# 50_Distance.net
KiCad netlist of a schematic drawn in Altium Designer
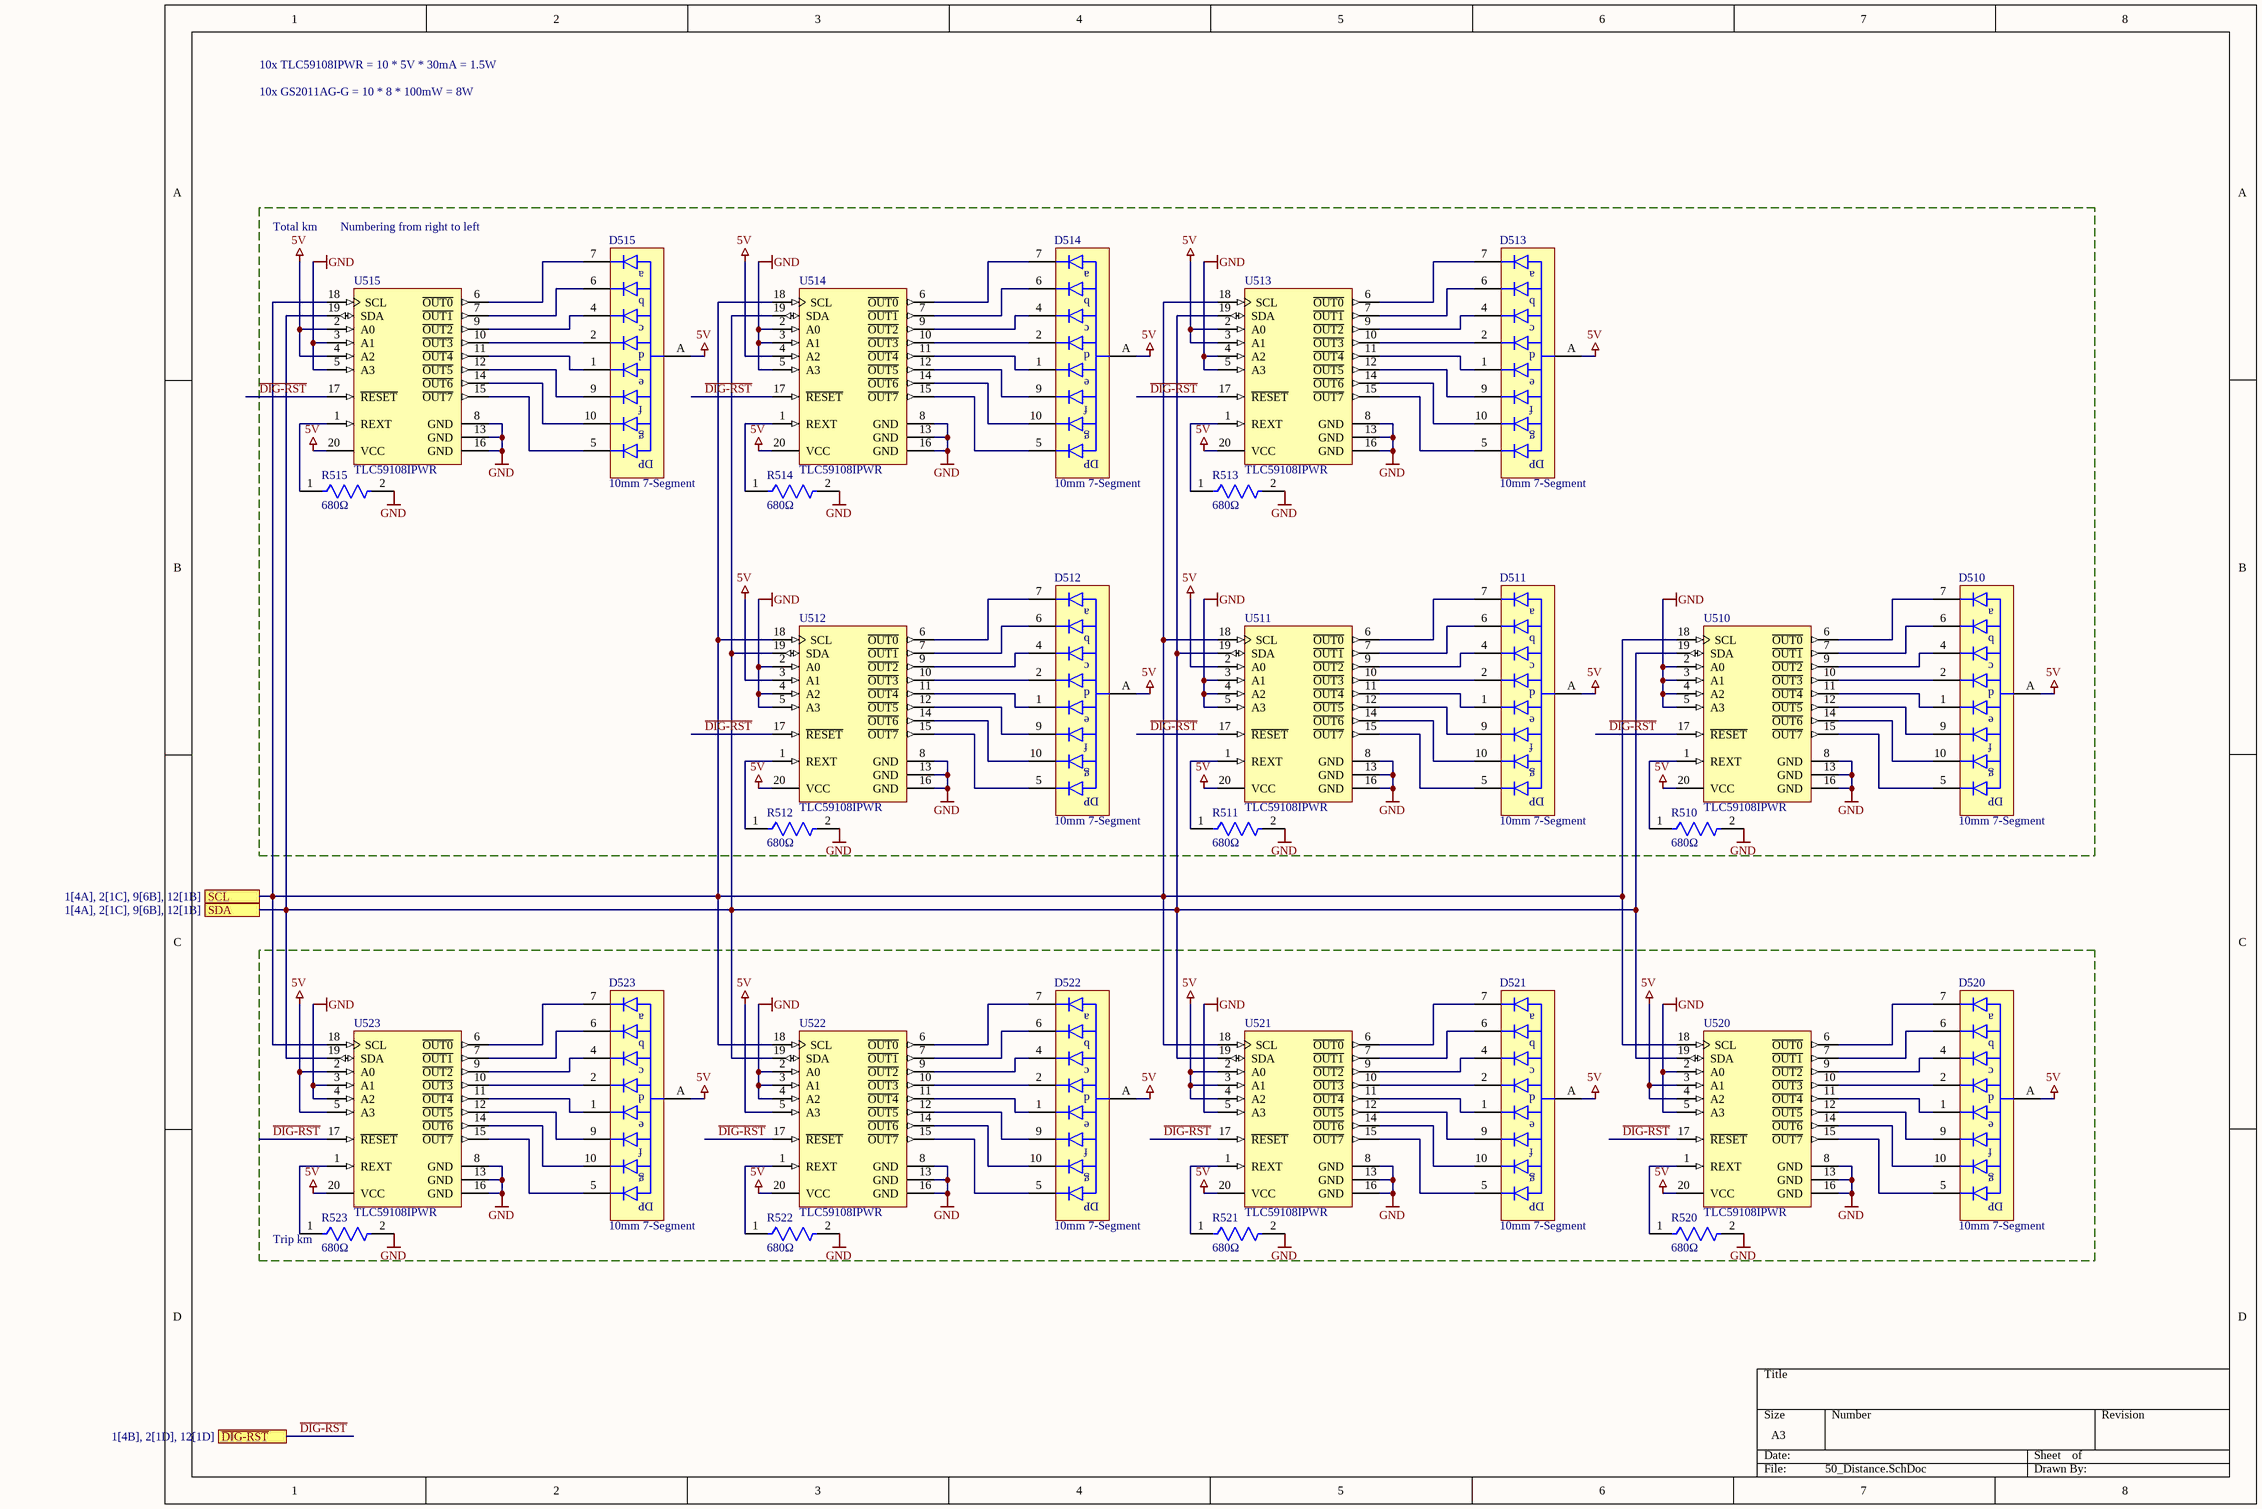
[diagram p0: 50_Distance.SchDoc]

(export (version "E")
  (design (tool "Eeschema 10.0.6"))
  (components
    (comp (ref "D510")
      (value "10mm 7-Segment")
      (footprint "GS2011AG-G")
      (description "SMD, 10x6.9mm 7-Segment")
      (libsource (lib "AltiumLib_MILUTIN") (part "GS2011AG-G"))
    )
    (comp (ref "D511")
      (value "10mm 7-Segment")
      (footprint "GS2011AG-G")
      (description "SMD, 10x6.9mm 7-Segment")
      (libsource (lib "AltiumLib_MILUTIN") (part "GS2011AG-G"))
    )
    (comp (ref "D512")
      (value "10mm 7-Segment")
      (footprint "GS2011AG-G")
      (description "SMD, 10x6.9mm 7-Segment")
      (libsource (lib "AltiumLib_MILUTIN") (part "GS2011AG-G"))
    )
    (comp (ref "D513")
      (value "10mm 7-Segment")
      (footprint "GS2011AG-G")
      (description "SMD, 10x6.9mm 7-Segment")
      (libsource (lib "AltiumLib_MILUTIN") (part "GS2011AG-G"))
    )
    (comp (ref "D514")
      (value "10mm 7-Segment")
      (footprint "GS2011AG-G")
      (description "SMD, 10x6.9mm 7-Segment")
      (libsource (lib "AltiumLib_MILUTIN") (part "GS2011AG-G"))
    )
    (comp (ref "D515")
      (value "10mm 7-Segment")
      (footprint "GS2011AG-G")
      (description "SMD, 10x6.9mm 7-Segment")
      (libsource (lib "AltiumLib_MILUTIN") (part "GS2011AG-G"))
    )
    (comp (ref "D520")
      (value "10mm 7-Segment")
      (footprint "GS2011AG-G")
      (description "SMD, 10x6.9mm 7-Segment")
      (libsource (lib "AltiumLib_MILUTIN") (part "GS2011AG-G"))
    )
    (comp (ref "D521")
      (value "10mm 7-Segment")
      (footprint "GS2011AG-G")
      (description "SMD, 10x6.9mm 7-Segment")
      (libsource (lib "AltiumLib_MILUTIN") (part "GS2011AG-G"))
    )
    (comp (ref "D522")
      (value "10mm 7-Segment")
      (footprint "GS2011AG-G")
      (description "SMD, 10x6.9mm 7-Segment")
      (libsource (lib "AltiumLib_MILUTIN") (part "GS2011AG-G"))
    )
    (comp (ref "D523")
      (value "10mm 7-Segment")
      (footprint "GS2011AG-G")
      (description "SMD, 10x6.9mm 7-Segment")
      (libsource (lib "AltiumLib_MILUTIN") (part "GS2011AG-G"))
    )
    (comp (ref "R510")
      (value "680Ω")
      (footprint "FP-CRCW0603-e3-IPC_A")
      (description "RES Thick Film, 680Ω, 5%, 0.1W, 200ppm/°C, 0603\r\nCRCW0603680RJNEA")
      (fields (field (name "TOLERANCE") "5%"))
      (libsource (lib "Altium Content Vault") (part "1029c3af85768c4190bb7ad29bc67b5"))
    )
    (comp (ref "R511")
      (value "680Ω")
      (footprint "FP-CRCW0603-e3-IPC_A")
      (description "RES Thick Film, 680Ω, 5%, 0.1W, 200ppm/°C, 0603\r\nCRCW0603680RJNEA")
      (fields (field (name "TOLERANCE") "5%"))
      (libsource (lib "Altium Content Vault") (part "1029c3af85768c4190bb7ad29bc67b5"))
    )
    (comp (ref "R512")
      (value "680Ω")
      (footprint "FP-CRCW0603-e3-IPC_A")
      (description "RES Thick Film, 680Ω, 5%, 0.1W, 200ppm/°C, 0603\r\nCRCW0603680RJNEA")
      (fields (field (name "TOLERANCE") "5%"))
      (libsource (lib "Altium Content Vault") (part "1029c3af85768c4190bb7ad29bc67b5"))
    )
    (comp (ref "R513")
      (value "680Ω")
      (footprint "FP-CRCW0603-e3-IPC_A")
      (description "RES Thick Film, 680Ω, 5%, 0.1W, 200ppm/°C, 0603\r\nCRCW0603680RJNEA")
      (fields (field (name "TOLERANCE") "5%"))
      (libsource (lib "Altium Content Vault") (part "1029c3af85768c4190bb7ad29bc67b5"))
    )
    (comp (ref "R514")
      (value "680Ω")
      (footprint "FP-CRCW0603-e3-IPC_A")
      (description "RES Thick Film, 680Ω, 5%, 0.1W, 200ppm/°C, 0603\r\nCRCW0603680RJNEA")
      (fields (field (name "TOLERANCE") "5%"))
      (libsource (lib "Altium Content Vault") (part "1029c3af85768c4190bb7ad29bc67b5"))
    )
    (comp (ref "R515")
      (value "680Ω")
      (footprint "FP-CRCW0603-e3-IPC_A")
      (description "RES Thick Film, 680Ω, 5%, 0.1W, 200ppm/°C, 0603\r\nCRCW0603680RJNEA")
      (fields (field (name "TOLERANCE") "5%"))
      (libsource (lib "Altium Content Vault") (part "1029c3af85768c4190bb7ad29bc67b5"))
    )
    (comp (ref "R520")
      (value "680Ω")
      (footprint "FP-CRCW0603-e3-IPC_A")
      (description "RES Thick Film, 680Ω, 5%, 0.1W, 200ppm/°C, 0603\r\nCRCW0603680RJNEA")
      (fields (field (name "TOLERANCE") "5%"))
      (libsource (lib "Altium Content Vault") (part "1029c3af85768c4190bb7ad29bc67b5"))
    )
    (comp (ref "R521")
      (value "680Ω")
      (footprint "FP-CRCW0603-e3-IPC_A")
      (description "RES Thick Film, 680Ω, 5%, 0.1W, 200ppm/°C, 0603\r\nCRCW0603680RJNEA")
      (fields (field (name "TOLERANCE") "5%"))
      (libsource (lib "Altium Content Vault") (part "1029c3af85768c4190bb7ad29bc67b5"))
    )
    (comp (ref "R522")
      (value "680Ω")
      (footprint "FP-CRCW0603-e3-IPC_A")
      (description "RES Thick Film, 680Ω, 5%, 0.1W, 200ppm/°C, 0603\r\nCRCW0603680RJNEA")
      (fields (field (name "TOLERANCE") "5%"))
      (libsource (lib "Altium Content Vault") (part "1029c3af85768c4190bb7ad29bc67b5"))
    )
    (comp (ref "R523")
      (value "680Ω")
      (footprint "FP-CRCW0603-e3-IPC_A")
      (description "RES Thick Film, 680Ω, 5%, 0.1W, 200ppm/°C, 0603\r\nCRCW0603680RJNEA")
      (fields (field (name "TOLERANCE") "5%"))
      (libsource (lib "Altium Content Vault") (part "1029c3af85768c4190bb7ad29bc67b5"))
    )
    (comp (ref "U510")
      (value "TLC59108IPWR")
      (footprint "PW0020A_M")
      (fields (field (name "MANUFACTURER") "Texas Instruments"))
      (libsource (lib "Altium Content Vault") (part "TI-TLC59108PW20"))
    )
    (comp (ref "U511")
      (value "TLC59108IPWR")
      (footprint "PW0020A_M")
      (fields (field (name "MANUFACTURER") "Texas Instruments"))
      (libsource (lib "Altium Content Vault") (part "TI-TLC59108PW20"))
    )
    (comp (ref "U512")
      (value "TLC59108IPWR")
      (footprint "PW0020A_M")
      (fields (field (name "MANUFACTURER") "Texas Instruments"))
      (libsource (lib "Altium Content Vault") (part "TI-TLC59108PW20"))
    )
    (comp (ref "U513")
      (value "TLC59108IPWR")
      (footprint "PW0020A_M")
      (fields (field (name "MANUFACTURER") "Texas Instruments"))
      (libsource (lib "Altium Content Vault") (part "TI-TLC59108PW20"))
    )
    (comp (ref "U514")
      (value "TLC59108IPWR")
      (footprint "PW0020A_M")
      (fields (field (name "MANUFACTURER") "Texas Instruments"))
      (libsource (lib "Altium Content Vault") (part "TI-TLC59108PW20"))
    )
    (comp (ref "U515")
      (value "TLC59108IPWR")
      (footprint "PW0020A_M")
      (fields (field (name "MANUFACTURER") "Texas Instruments"))
      (libsource (lib "Altium Content Vault") (part "TI-TLC59108PW20"))
    )
    (comp (ref "U520")
      (value "TLC59108IPWR")
      (footprint "PW0020A_M")
      (fields (field (name "MANUFACTURER") "Texas Instruments"))
      (libsource (lib "Altium Content Vault") (part "TI-TLC59108PW20"))
    )
    (comp (ref "U521")
      (value "TLC59108IPWR")
      (footprint "PW0020A_M")
      (fields (field (name "MANUFACTURER") "Texas Instruments"))
      (libsource (lib "Altium Content Vault") (part "TI-TLC59108PW20"))
    )
    (comp (ref "U522")
      (value "TLC59108IPWR")
      (footprint "PW0020A_M")
      (fields (field (name "MANUFACTURER") "Texas Instruments"))
      (libsource (lib "Altium Content Vault") (part "TI-TLC59108PW20"))
    )
    (comp (ref "U523")
      (value "TLC59108IPWR")
      (footprint "PW0020A_M")
      (fields (field (name "MANUFACTURER") "Texas Instruments"))
      (libsource (lib "Altium Content Vault") (part "TI-TLC59108PW20"))
    )
  )
  (nets
    (net (code "1") (name "/SCL") (class "Default")
      (node (ref "U510") (pin "18") (pinfunction "SCL_18") (pintype "input"))
      (node (ref "U511") (pin "18") (pinfunction "SCL_18") (pintype "input"))
      (node (ref "U512") (pin "18") (pinfunction "SCL_18") (pintype "input"))
      (node (ref "U513") (pin "18") (pinfunction "SCL_18") (pintype "input"))
      (node (ref "U514") (pin "18") (pinfunction "SCL_18") (pintype "input"))
      (node (ref "U515") (pin "18") (pinfunction "SCL_18") (pintype "input"))
      (node (ref "U520") (pin "18") (pinfunction "SCL_18") (pintype "input"))
      (node (ref "U521") (pin "18") (pinfunction "SCL_18") (pintype "input"))
      (node (ref "U522") (pin "18") (pinfunction "SCL_18") (pintype "input"))
      (node (ref "U523") (pin "18") (pinfunction "SCL_18") (pintype "input"))
    )
    (net (code "2") (name "/SDA") (class "Default")
      (node (ref "U510") (pin "19") (pinfunction "SDA_19") (pintype "bidirectional"))
      (node (ref "U511") (pin "19") (pinfunction "SDA_19") (pintype "bidirectional"))
      (node (ref "U512") (pin "19") (pinfunction "SDA_19") (pintype "bidirectional"))
      (node (ref "U513") (pin "19") (pinfunction "SDA_19") (pintype "bidirectional"))
      (node (ref "U514") (pin "19") (pinfunction "SDA_19") (pintype "bidirectional"))
      (node (ref "U515") (pin "19") (pinfunction "SDA_19") (pintype "bidirectional"))
      (node (ref "U520") (pin "19") (pinfunction "SDA_19") (pintype "bidirectional"))
      (node (ref "U521") (pin "19") (pinfunction "SDA_19") (pintype "bidirectional"))
      (node (ref "U522") (pin "19") (pinfunction "SDA_19") (pintype "bidirectional"))
      (node (ref "U523") (pin "19") (pinfunction "SDA_19") (pintype "bidirectional"))
    )
    (net (code "3") (name "/~{DIG-RST}") (class "Default")
      (node (ref "U510") (pin "17") (pinfunction "~{RESET}_17") (pintype "input"))
      (node (ref "U511") (pin "17") (pinfunction "~{RESET}_17") (pintype "input"))
      (node (ref "U512") (pin "17") (pinfunction "~{RESET}_17") (pintype "input"))
      (node (ref "U513") (pin "17") (pinfunction "~{RESET}_17") (pintype "input"))
      (node (ref "U514") (pin "17") (pinfunction "~{RESET}_17") (pintype "input"))
      (node (ref "U515") (pin "17") (pinfunction "~{RESET}_17") (pintype "input"))
      (node (ref "U520") (pin "17") (pinfunction "~{RESET}_17") (pintype "input"))
      (node (ref "U521") (pin "17") (pinfunction "~{RESET}_17") (pintype "input"))
      (node (ref "U522") (pin "17") (pinfunction "~{RESET}_17") (pintype "input"))
      (node (ref "U523") (pin "17") (pinfunction "~{RESET}_17") (pintype "input"))
    )
    (net (code "4") (name "5V") (class "Default")
      (node (ref "D510") (pin "A") (pinfunction "A_A") (pintype "passive"))
      (node (ref "D511") (pin "A") (pinfunction "A_A") (pintype "passive"))
      (node (ref "D512") (pin "A") (pinfunction "A_A") (pintype "passive"))
      (node (ref "D513") (pin "A") (pinfunction "A_A") (pintype "passive"))
      (node (ref "D514") (pin "A") (pinfunction "A_A") (pintype "passive"))
      (node (ref "D515") (pin "A") (pinfunction "A_A") (pintype "passive"))
      (node (ref "D520") (pin "A") (pinfunction "A_A") (pintype "passive"))
      (node (ref "D521") (pin "A") (pinfunction "A_A") (pintype "passive"))
      (node (ref "D522") (pin "A") (pinfunction "A_A") (pintype "passive"))
      (node (ref "D523") (pin "A") (pinfunction "A_A") (pintype "passive"))
      (node (ref "U510") (pin "20") (pinfunction "VCC_20") (pintype "power_in"))
      (node (ref "U511") (pin "2") (pinfunction "A0_2") (pintype "input"))
      (node (ref "U511") (pin "20") (pinfunction "VCC_20") (pintype "power_in"))
      (node (ref "U512") (pin "20") (pinfunction "VCC_20") (pintype "power_in"))
      (node (ref "U512") (pin "3") (pinfunction "A1_3") (pintype "input"))
      (node (ref "U513") (pin "2") (pinfunction "A0_2") (pintype "input"))
      (node (ref "U513") (pin "20") (pinfunction "VCC_20") (pintype "power_in"))
      (node (ref "U513") (pin "3") (pinfunction "A1_3") (pintype "input"))
      (node (ref "U514") (pin "20") (pinfunction "VCC_20") (pintype "power_in"))
      (node (ref "U514") (pin "4") (pinfunction "A2_4") (pintype "input"))
      (node (ref "U515") (pin "2") (pinfunction "A0_2") (pintype "input"))
      (node (ref "U515") (pin "20") (pinfunction "VCC_20") (pintype "power_in"))
      (node (ref "U515") (pin "4") (pinfunction "A2_4") (pintype "input"))
      (node (ref "U520") (pin "20") (pinfunction "VCC_20") (pintype "power_in"))
      (node (ref "U520") (pin "3") (pinfunction "A1_3") (pintype "input"))
      (node (ref "U520") (pin "4") (pinfunction "A2_4") (pintype "input"))
      (node (ref "U521") (pin "2") (pinfunction "A0_2") (pintype "input"))
      (node (ref "U521") (pin "20") (pinfunction "VCC_20") (pintype "power_in"))
      (node (ref "U521") (pin "3") (pinfunction "A1_3") (pintype "input"))
      (node (ref "U521") (pin "4") (pinfunction "A2_4") (pintype "input"))
      (node (ref "U522") (pin "20") (pinfunction "VCC_20") (pintype "power_in"))
      (node (ref "U522") (pin "5") (pinfunction "A3_5") (pintype "input"))
      (node (ref "U523") (pin "2") (pinfunction "A0_2") (pintype "input"))
      (node (ref "U523") (pin "20") (pinfunction "VCC_20") (pintype "power_in"))
      (node (ref "U523") (pin "5") (pinfunction "A3_5") (pintype "input"))
    )
    (net (code "5") (name "GND") (class "Default")
      (node (ref "R510") (pin "2") (pinfunction "2_2") (pintype "passive"))
      (node (ref "R511") (pin "2") (pinfunction "2_2") (pintype "passive"))
      (node (ref "R512") (pin "2") (pinfunction "2_2") (pintype "passive"))
      (node (ref "R513") (pin "2") (pinfunction "2_2") (pintype "passive"))
      (node (ref "R514") (pin "2") (pinfunction "2_2") (pintype "passive"))
      (node (ref "R515") (pin "2") (pinfunction "2_2") (pintype "passive"))
      (node (ref "R520") (pin "2") (pinfunction "2_2") (pintype "passive"))
      (node (ref "R521") (pin "2") (pinfunction "2_2") (pintype "passive"))
      (node (ref "R522") (pin "2") (pinfunction "2_2") (pintype "passive"))
      (node (ref "R523") (pin "2") (pinfunction "2_2") (pintype "passive"))
      (node (ref "U510") (pin "13") (pinfunction "GND_13") (pintype "power_in"))
      (node (ref "U510") (pin "16") (pinfunction "GND_16") (pintype "power_in"))
      (node (ref "U510") (pin "2") (pinfunction "A0_2") (pintype "input"))
      (node (ref "U510") (pin "3") (pinfunction "A1_3") (pintype "input"))
      (node (ref "U510") (pin "4") (pinfunction "A2_4") (pintype "input"))
      (node (ref "U510") (pin "5") (pinfunction "A3_5") (pintype "input"))
      (node (ref "U510") (pin "8") (pinfunction "GND_8") (pintype "power_in"))
      (node (ref "U511") (pin "13") (pinfunction "GND_13") (pintype "power_in"))
      (node (ref "U511") (pin "16") (pinfunction "GND_16") (pintype "power_in"))
      (node (ref "U511") (pin "3") (pinfunction "A1_3") (pintype "input"))
      (node (ref "U511") (pin "4") (pinfunction "A2_4") (pintype "input"))
      (node (ref "U511") (pin "5") (pinfunction "A3_5") (pintype "input"))
      (node (ref "U511") (pin "8") (pinfunction "GND_8") (pintype "power_in"))
      (node (ref "U512") (pin "13") (pinfunction "GND_13") (pintype "power_in"))
      (node (ref "U512") (pin "16") (pinfunction "GND_16") (pintype "power_in"))
      (node (ref "U512") (pin "2") (pinfunction "A0_2") (pintype "input"))
      (node (ref "U512") (pin "4") (pinfunction "A2_4") (pintype "input"))
      (node (ref "U512") (pin "5") (pinfunction "A3_5") (pintype "input"))
      (node (ref "U512") (pin "8") (pinfunction "GND_8") (pintype "power_in"))
      (node (ref "U513") (pin "13") (pinfunction "GND_13") (pintype "power_in"))
      (node (ref "U513") (pin "16") (pinfunction "GND_16") (pintype "power_in"))
      (node (ref "U513") (pin "4") (pinfunction "A2_4") (pintype "input"))
      (node (ref "U513") (pin "5") (pinfunction "A3_5") (pintype "input"))
      (node (ref "U513") (pin "8") (pinfunction "GND_8") (pintype "power_in"))
      (node (ref "U514") (pin "13") (pinfunction "GND_13") (pintype "power_in"))
      (node (ref "U514") (pin "16") (pinfunction "GND_16") (pintype "power_in"))
      (node (ref "U514") (pin "2") (pinfunction "A0_2") (pintype "input"))
      (node (ref "U514") (pin "3") (pinfunction "A1_3") (pintype "input"))
      (node (ref "U514") (pin "5") (pinfunction "A3_5") (pintype "input"))
      (node (ref "U514") (pin "8") (pinfunction "GND_8") (pintype "power_in"))
      (node (ref "U515") (pin "13") (pinfunction "GND_13") (pintype "power_in"))
      (node (ref "U515") (pin "16") (pinfunction "GND_16") (pintype "power_in"))
      (node (ref "U515") (pin "3") (pinfunction "A1_3") (pintype "input"))
      (node (ref "U515") (pin "5") (pinfunction "A3_5") (pintype "input"))
      (node (ref "U515") (pin "8") (pinfunction "GND_8") (pintype "power_in"))
      (node (ref "U520") (pin "13") (pinfunction "GND_13") (pintype "power_in"))
      (node (ref "U520") (pin "16") (pinfunction "GND_16") (pintype "power_in"))
      (node (ref "U520") (pin "2") (pinfunction "A0_2") (pintype "input"))
      (node (ref "U520") (pin "5") (pinfunction "A3_5") (pintype "input"))
      (node (ref "U520") (pin "8") (pinfunction "GND_8") (pintype "power_in"))
      (node (ref "U521") (pin "13") (pinfunction "GND_13") (pintype "power_in"))
      (node (ref "U521") (pin "16") (pinfunction "GND_16") (pintype "power_in"))
      (node (ref "U521") (pin "5") (pinfunction "A3_5") (pintype "input"))
      (node (ref "U521") (pin "8") (pinfunction "GND_8") (pintype "power_in"))
      (node (ref "U522") (pin "13") (pinfunction "GND_13") (pintype "power_in"))
      (node (ref "U522") (pin "16") (pinfunction "GND_16") (pintype "power_in"))
      (node (ref "U522") (pin "2") (pinfunction "A0_2") (pintype "input"))
      (node (ref "U522") (pin "3") (pinfunction "A1_3") (pintype "input"))
      (node (ref "U522") (pin "4") (pinfunction "A2_4") (pintype "input"))
      (node (ref "U522") (pin "8") (pinfunction "GND_8") (pintype "power_in"))
      (node (ref "U523") (pin "13") (pinfunction "GND_13") (pintype "power_in"))
      (node (ref "U523") (pin "16") (pinfunction "GND_16") (pintype "power_in"))
      (node (ref "U523") (pin "3") (pinfunction "A1_3") (pintype "input"))
      (node (ref "U523") (pin "4") (pinfunction "A2_4") (pintype "input"))
      (node (ref "U523") (pin "8") (pinfunction "GND_8") (pintype "power_in"))
    )
    (net (code "6") (name "Net-(U510-REXT)") (class "Default")
      (node (ref "R510") (pin "1") (pinfunction "1_1") (pintype "passive"))
      (node (ref "U510") (pin "1") (pinfunction "REXT_1") (pintype "input"))
    )
    (net (code "7") (name "Net-(U510-~{OUT0})") (class "Default")
      (node (ref "D510") (pin "7") (pinfunction "7_7") (pintype "passive"))
      (node (ref "U510") (pin "6") (pinfunction "~{OUT0}_6") (pintype "output"))
    )
    (net (code "8") (name "Net-(U510-~{OUT1})") (class "Default")
      (node (ref "D510") (pin "6") (pinfunction "6_6") (pintype "passive"))
      (node (ref "U510") (pin "7") (pinfunction "~{OUT1}_7") (pintype "output"))
    )
    (net (code "9") (name "Net-(U510-~{OUT2})") (class "Default")
      (node (ref "D510") (pin "4") (pinfunction "4_4") (pintype "passive"))
      (node (ref "U510") (pin "9") (pinfunction "~{OUT2}_9") (pintype "output"))
    )
    (net (code "10") (name "Net-(U510-~{OUT3})") (class "Default")
      (node (ref "D510") (pin "2") (pinfunction "2_2") (pintype "passive"))
      (node (ref "U510") (pin "10") (pinfunction "~{OUT3}_10") (pintype "output"))
    )
    (net (code "11") (name "Net-(U510-~{OUT4})") (class "Default")
      (node (ref "D510") (pin "1") (pinfunction "1_1") (pintype "passive"))
      (node (ref "U510") (pin "11") (pinfunction "~{OUT4}_11") (pintype "output"))
    )
    (net (code "12") (name "Net-(U510-~{OUT5})") (class "Default")
      (node (ref "D510") (pin "9") (pinfunction "9_9") (pintype "passive"))
      (node (ref "U510") (pin "12") (pinfunction "~{OUT5}_12") (pintype "output"))
    )
    (net (code "13") (name "Net-(U510-~{OUT6})") (class "Default")
      (node (ref "D510") (pin "10") (pinfunction "10_10") (pintype "passive"))
      (node (ref "U510") (pin "14") (pinfunction "~{OUT6}_14") (pintype "output"))
    )
    (net (code "14") (name "Net-(U510-~{OUT7})") (class "Default")
      (node (ref "D510") (pin "5") (pinfunction "5_5") (pintype "passive"))
      (node (ref "U510") (pin "15") (pinfunction "~{OUT7}_15") (pintype "output"))
    )
    (net (code "15") (name "Net-(U511-REXT)") (class "Default")
      (node (ref "R511") (pin "1") (pinfunction "1_1") (pintype "passive"))
      (node (ref "U511") (pin "1") (pinfunction "REXT_1") (pintype "input"))
    )
    (net (code "16") (name "Net-(U511-~{OUT0})") (class "Default")
      (node (ref "D511") (pin "7") (pinfunction "7_7") (pintype "passive"))
      (node (ref "U511") (pin "6") (pinfunction "~{OUT0}_6") (pintype "output"))
    )
    (net (code "17") (name "Net-(U511-~{OUT1})") (class "Default")
      (node (ref "D511") (pin "6") (pinfunction "6_6") (pintype "passive"))
      (node (ref "U511") (pin "7") (pinfunction "~{OUT1}_7") (pintype "output"))
    )
    (net (code "18") (name "Net-(U511-~{OUT2})") (class "Default")
      (node (ref "D511") (pin "4") (pinfunction "4_4") (pintype "passive"))
      (node (ref "U511") (pin "9") (pinfunction "~{OUT2}_9") (pintype "output"))
    )
    (net (code "19") (name "Net-(U511-~{OUT3})") (class "Default")
      (node (ref "D511") (pin "2") (pinfunction "2_2") (pintype "passive"))
      (node (ref "U511") (pin "10") (pinfunction "~{OUT3}_10") (pintype "output"))
    )
    (net (code "20") (name "Net-(U511-~{OUT4})") (class "Default")
      (node (ref "D511") (pin "1") (pinfunction "1_1") (pintype "passive"))
      (node (ref "U511") (pin "11") (pinfunction "~{OUT4}_11") (pintype "output"))
    )
    (net (code "21") (name "Net-(U511-~{OUT5})") (class "Default")
      (node (ref "D511") (pin "9") (pinfunction "9_9") (pintype "passive"))
      (node (ref "U511") (pin "12") (pinfunction "~{OUT5}_12") (pintype "output"))
    )
    (net (code "22") (name "Net-(U511-~{OUT6})") (class "Default")
      (node (ref "D511") (pin "10") (pinfunction "10_10") (pintype "passive"))
      (node (ref "U511") (pin "14") (pinfunction "~{OUT6}_14") (pintype "output"))
    )
    (net (code "23") (name "Net-(U511-~{OUT7})") (class "Default")
      (node (ref "D511") (pin "5") (pinfunction "5_5") (pintype "passive"))
      (node (ref "U511") (pin "15") (pinfunction "~{OUT7}_15") (pintype "output"))
    )
    (net (code "24") (name "Net-(U512-REXT)") (class "Default")
      (node (ref "R512") (pin "1") (pinfunction "1_1") (pintype "passive"))
      (node (ref "U512") (pin "1") (pinfunction "REXT_1") (pintype "input"))
    )
    (net (code "25") (name "Net-(U512-~{OUT0})") (class "Default")
      (node (ref "D512") (pin "7") (pinfunction "7_7") (pintype "passive"))
      (node (ref "U512") (pin "6") (pinfunction "~{OUT0}_6") (pintype "output"))
    )
    (net (code "26") (name "Net-(U512-~{OUT1})") (class "Default")
      (node (ref "D512") (pin "6") (pinfunction "6_6") (pintype "passive"))
      (node (ref "U512") (pin "7") (pinfunction "~{OUT1}_7") (pintype "output"))
    )
    (net (code "27") (name "Net-(U512-~{OUT2})") (class "Default")
      (node (ref "D512") (pin "4") (pinfunction "4_4") (pintype "passive"))
      (node (ref "U512") (pin "9") (pinfunction "~{OUT2}_9") (pintype "output"))
    )
    (net (code "28") (name "Net-(U512-~{OUT3})") (class "Default")
      (node (ref "D512") (pin "2") (pinfunction "2_2") (pintype "passive"))
      (node (ref "U512") (pin "10") (pinfunction "~{OUT3}_10") (pintype "output"))
    )
    (net (code "29") (name "Net-(U512-~{OUT4})") (class "Default")
      (node (ref "D512") (pin "1") (pinfunction "1_1") (pintype "passive"))
      (node (ref "U512") (pin "11") (pinfunction "~{OUT4}_11") (pintype "output"))
    )
    (net (code "30") (name "Net-(U512-~{OUT5})") (class "Default")
      (node (ref "D512") (pin "9") (pinfunction "9_9") (pintype "passive"))
      (node (ref "U512") (pin "12") (pinfunction "~{OUT5}_12") (pintype "output"))
    )
    (net (code "31") (name "Net-(U512-~{OUT6})") (class "Default")
      (node (ref "D512") (pin "10") (pinfunction "10_10") (pintype "passive"))
      (node (ref "U512") (pin "14") (pinfunction "~{OUT6}_14") (pintype "output"))
    )
    (net (code "32") (name "Net-(U512-~{OUT7})") (class "Default")
      (node (ref "D512") (pin "5") (pinfunction "5_5") (pintype "passive"))
      (node (ref "U512") (pin "15") (pinfunction "~{OUT7}_15") (pintype "output"))
    )
    (net (code "33") (name "Net-(U513-REXT)") (class "Default")
      (node (ref "R513") (pin "1") (pinfunction "1_1") (pintype "passive"))
      (node (ref "U513") (pin "1") (pinfunction "REXT_1") (pintype "input"))
    )
    (net (code "34") (name "Net-(U513-~{OUT0})") (class "Default")
      (node (ref "D513") (pin "7") (pinfunction "7_7") (pintype "passive"))
      (node (ref "U513") (pin "6") (pinfunction "~{OUT0}_6") (pintype "output"))
    )
    (net (code "35") (name "Net-(U513-~{OUT1})") (class "Default")
      (node (ref "D513") (pin "6") (pinfunction "6_6") (pintype "passive"))
      (node (ref "U513") (pin "7") (pinfunction "~{OUT1}_7") (pintype "output"))
    )
    (net (code "36") (name "Net-(U513-~{OUT2})") (class "Default")
      (node (ref "D513") (pin "4") (pinfunction "4_4") (pintype "passive"))
      (node (ref "U513") (pin "9") (pinfunction "~{OUT2}_9") (pintype "output"))
    )
    (net (code "37") (name "Net-(U513-~{OUT3})") (class "Default")
      (node (ref "D513") (pin "2") (pinfunction "2_2") (pintype "passive"))
      (node (ref "U513") (pin "10") (pinfunction "~{OUT3}_10") (pintype "output"))
    )
    (net (code "38") (name "Net-(U513-~{OUT4})") (class "Default")
      (node (ref "D513") (pin "1") (pinfunction "1_1") (pintype "passive"))
      (node (ref "U513") (pin "11") (pinfunction "~{OUT4}_11") (pintype "output"))
    )
    (net (code "39") (name "Net-(U513-~{OUT5})") (class "Default")
      (node (ref "D513") (pin "9") (pinfunction "9_9") (pintype "passive"))
      (node (ref "U513") (pin "12") (pinfunction "~{OUT5}_12") (pintype "output"))
    )
    (net (code "40") (name "Net-(U513-~{OUT6})") (class "Default")
      (node (ref "D513") (pin "10") (pinfunction "10_10") (pintype "passive"))
      (node (ref "U513") (pin "14") (pinfunction "~{OUT6}_14") (pintype "output"))
    )
    (net (code "41") (name "Net-(U513-~{OUT7})") (class "Default")
      (node (ref "D513") (pin "5") (pinfunction "5_5") (pintype "passive"))
      (node (ref "U513") (pin "15") (pinfunction "~{OUT7}_15") (pintype "output"))
    )
    (net (code "42") (name "Net-(U514-REXT)") (class "Default")
      (node (ref "R514") (pin "1") (pinfunction "1_1") (pintype "passive"))
      (node (ref "U514") (pin "1") (pinfunction "REXT_1") (pintype "input"))
    )
    (net (code "43") (name "Net-(U514-~{OUT0})") (class "Default")
      (node (ref "D514") (pin "7") (pinfunction "7_7") (pintype "passive"))
      (node (ref "U514") (pin "6") (pinfunction "~{OUT0}_6") (pintype "output"))
    )
    (net (code "44") (name "Net-(U514-~{OUT1})") (class "Default")
      (node (ref "D514") (pin "6") (pinfunction "6_6") (pintype "passive"))
      (node (ref "U514") (pin "7") (pinfunction "~{OUT1}_7") (pintype "output"))
    )
    (net (code "45") (name "Net-(U514-~{OUT2})") (class "Default")
      (node (ref "D514") (pin "4") (pinfunction "4_4") (pintype "passive"))
      (node (ref "U514") (pin "9") (pinfunction "~{OUT2}_9") (pintype "output"))
    )
    (net (code "46") (name "Net-(U514-~{OUT3})") (class "Default")
      (node (ref "D514") (pin "2") (pinfunction "2_2") (pintype "passive"))
      (node (ref "U514") (pin "10") (pinfunction "~{OUT3}_10") (pintype "output"))
    )
    (net (code "47") (name "Net-(U514-~{OUT4})") (class "Default")
      (node (ref "D514") (pin "1") (pinfunction "1_1") (pintype "passive"))
      (node (ref "U514") (pin "11") (pinfunction "~{OUT4}_11") (pintype "output"))
    )
    (net (code "48") (name "Net-(U514-~{OUT5})") (class "Default")
      (node (ref "D514") (pin "9") (pinfunction "9_9") (pintype "passive"))
      (node (ref "U514") (pin "12") (pinfunction "~{OUT5}_12") (pintype "output"))
    )
    (net (code "49") (name "Net-(U514-~{OUT6})") (class "Default")
      (node (ref "D514") (pin "10") (pinfunction "10_10") (pintype "passive"))
      (node (ref "U514") (pin "14") (pinfunction "~{OUT6}_14") (pintype "output"))
    )
    (net (code "50") (name "Net-(U514-~{OUT7})") (class "Default")
      (node (ref "D514") (pin "5") (pinfunction "5_5") (pintype "passive"))
      (node (ref "U514") (pin "15") (pinfunction "~{OUT7}_15") (pintype "output"))
    )
    (net (code "51") (name "Net-(U515-REXT)") (class "Default")
      (node (ref "R515") (pin "1") (pinfunction "1_1") (pintype "passive"))
      (node (ref "U515") (pin "1") (pinfunction "REXT_1") (pintype "input"))
    )
    (net (code "52") (name "Net-(U515-~{OUT0})") (class "Default")
      (node (ref "D515") (pin "7") (pinfunction "7_7") (pintype "passive"))
      (node (ref "U515") (pin "6") (pinfunction "~{OUT0}_6") (pintype "output"))
    )
    (net (code "53") (name "Net-(U515-~{OUT1})") (class "Default")
      (node (ref "D515") (pin "6") (pinfunction "6_6") (pintype "passive"))
      (node (ref "U515") (pin "7") (pinfunction "~{OUT1}_7") (pintype "output"))
    )
    (net (code "54") (name "Net-(U515-~{OUT2})") (class "Default")
      (node (ref "D515") (pin "4") (pinfunction "4_4") (pintype "passive"))
      (node (ref "U515") (pin "9") (pinfunction "~{OUT2}_9") (pintype "output"))
    )
    (net (code "55") (name "Net-(U515-~{OUT3})") (class "Default")
      (node (ref "D515") (pin "2") (pinfunction "2_2") (pintype "passive"))
      (node (ref "U515") (pin "10") (pinfunction "~{OUT3}_10") (pintype "output"))
    )
    (net (code "56") (name "Net-(U515-~{OUT4})") (class "Default")
      (node (ref "D515") (pin "1") (pinfunction "1_1") (pintype "passive"))
      (node (ref "U515") (pin "11") (pinfunction "~{OUT4}_11") (pintype "output"))
    )
    (net (code "57") (name "Net-(U515-~{OUT5})") (class "Default")
      (node (ref "D515") (pin "9") (pinfunction "9_9") (pintype "passive"))
      (node (ref "U515") (pin "12") (pinfunction "~{OUT5}_12") (pintype "output"))
    )
    (net (code "58") (name "Net-(U515-~{OUT6})") (class "Default")
      (node (ref "D515") (pin "10") (pinfunction "10_10") (pintype "passive"))
      (node (ref "U515") (pin "14") (pinfunction "~{OUT6}_14") (pintype "output"))
    )
    (net (code "59") (name "Net-(U515-~{OUT7})") (class "Default")
      (node (ref "D515") (pin "5") (pinfunction "5_5") (pintype "passive"))
      (node (ref "U515") (pin "15") (pinfunction "~{OUT7}_15") (pintype "output"))
    )
    (net (code "60") (name "Net-(U520-REXT)") (class "Default")
      (node (ref "R520") (pin "1") (pinfunction "1_1") (pintype "passive"))
      (node (ref "U520") (pin "1") (pinfunction "REXT_1") (pintype "input"))
    )
    (net (code "61") (name "Net-(U520-~{OUT0})") (class "Default")
      (node (ref "D520") (pin "7") (pinfunction "7_7") (pintype "passive"))
      (node (ref "U520") (pin "6") (pinfunction "~{OUT0}_6") (pintype "output"))
    )
    (net (code "62") (name "Net-(U520-~{OUT1})") (class "Default")
      (node (ref "D520") (pin "6") (pinfunction "6_6") (pintype "passive"))
      (node (ref "U520") (pin "7") (pinfunction "~{OUT1}_7") (pintype "output"))
    )
    (net (code "63") (name "Net-(U520-~{OUT2})") (class "Default")
      (node (ref "D520") (pin "4") (pinfunction "4_4") (pintype "passive"))
      (node (ref "U520") (pin "9") (pinfunction "~{OUT2}_9") (pintype "output"))
    )
    (net (code "64") (name "Net-(U520-~{OUT3})") (class "Default")
      (node (ref "D520") (pin "2") (pinfunction "2_2") (pintype "passive"))
      (node (ref "U520") (pin "10") (pinfunction "~{OUT3}_10") (pintype "output"))
    )
    (net (code "65") (name "Net-(U520-~{OUT4})") (class "Default")
      (node (ref "D520") (pin "1") (pinfunction "1_1") (pintype "passive"))
      (node (ref "U520") (pin "11") (pinfunction "~{OUT4}_11") (pintype "output"))
    )
    (net (code "66") (name "Net-(U520-~{OUT5})") (class "Default")
      (node (ref "D520") (pin "9") (pinfunction "9_9") (pintype "passive"))
      (node (ref "U520") (pin "12") (pinfunction "~{OUT5}_12") (pintype "output"))
    )
    (net (code "67") (name "Net-(U520-~{OUT6})") (class "Default")
      (node (ref "D520") (pin "10") (pinfunction "10_10") (pintype "passive"))
      (node (ref "U520") (pin "14") (pinfunction "~{OUT6}_14") (pintype "output"))
    )
    (net (code "68") (name "Net-(U520-~{OUT7})") (class "Default")
      (node (ref "D520") (pin "5") (pinfunction "5_5") (pintype "passive"))
      (node (ref "U520") (pin "15") (pinfunction "~{OUT7}_15") (pintype "output"))
    )
    (net (code "69") (name "Net-(U521-REXT)") (class "Default")
      (node (ref "R521") (pin "1") (pinfunction "1_1") (pintype "passive"))
      (node (ref "U521") (pin "1") (pinfunction "REXT_1") (pintype "input"))
    )
    (net (code "70") (name "Net-(U521-~{OUT0})") (class "Default")
      (node (ref "D521") (pin "7") (pinfunction "7_7") (pintype "passive"))
      (node (ref "U521") (pin "6") (pinfunction "~{OUT0}_6") (pintype "output"))
    )
    (net (code "71") (name "Net-(U521-~{OUT1})") (class "Default")
      (node (ref "D521") (pin "6") (pinfunction "6_6") (pintype "passive"))
      (node (ref "U521") (pin "7") (pinfunction "~{OUT1}_7") (pintype "output"))
    )
    (net (code "72") (name "Net-(U521-~{OUT2})") (class "Default")
      (node (ref "D521") (pin "4") (pinfunction "4_4") (pintype "passive"))
      (node (ref "U521") (pin "9") (pinfunction "~{OUT2}_9") (pintype "output"))
    )
    (net (code "73") (name "Net-(U521-~{OUT3})") (class "Default")
      (node (ref "D521") (pin "2") (pinfunction "2_2") (pintype "passive"))
      (node (ref "U521") (pin "10") (pinfunction "~{OUT3}_10") (pintype "output"))
    )
    (net (code "74") (name "Net-(U521-~{OUT4})") (class "Default")
      (node (ref "D521") (pin "1") (pinfunction "1_1") (pintype "passive"))
      (node (ref "U521") (pin "11") (pinfunction "~{OUT4}_11") (pintype "output"))
    )
    (net (code "75") (name "Net-(U521-~{OUT5})") (class "Default")
      (node (ref "D521") (pin "9") (pinfunction "9_9") (pintype "passive"))
      (node (ref "U521") (pin "12") (pinfunction "~{OUT5}_12") (pintype "output"))
    )
    (net (code "76") (name "Net-(U521-~{OUT6})") (class "Default")
      (node (ref "D521") (pin "10") (pinfunction "10_10") (pintype "passive"))
      (node (ref "U521") (pin "14") (pinfunction "~{OUT6}_14") (pintype "output"))
    )
    (net (code "77") (name "Net-(U521-~{OUT7})") (class "Default")
      (node (ref "D521") (pin "5") (pinfunction "5_5") (pintype "passive"))
      (node (ref "U521") (pin "15") (pinfunction "~{OUT7}_15") (pintype "output"))
    )
    (net (code "78") (name "Net-(U522-REXT)") (class "Default")
      (node (ref "R522") (pin "1") (pinfunction "1_1") (pintype "passive"))
      (node (ref "U522") (pin "1") (pinfunction "REXT_1") (pintype "input"))
    )
    (net (code "79") (name "Net-(U522-~{OUT0})") (class "Default")
      (node (ref "D522") (pin "7") (pinfunction "7_7") (pintype "passive"))
      (node (ref "U522") (pin "6") (pinfunction "~{OUT0}_6") (pintype "output"))
    )
    (net (code "80") (name "Net-(U522-~{OUT1})") (class "Default")
      (node (ref "D522") (pin "6") (pinfunction "6_6") (pintype "passive"))
      (node (ref "U522") (pin "7") (pinfunction "~{OUT1}_7") (pintype "output"))
    )
    (net (code "81") (name "Net-(U522-~{OUT2})") (class "Default")
      (node (ref "D522") (pin "4") (pinfunction "4_4") (pintype "passive"))
      (node (ref "U522") (pin "9") (pinfunction "~{OUT2}_9") (pintype "output"))
    )
    (net (code "82") (name "Net-(U522-~{OUT3})") (class "Default")
      (node (ref "D522") (pin "2") (pinfunction "2_2") (pintype "passive"))
      (node (ref "U522") (pin "10") (pinfunction "~{OUT3}_10") (pintype "output"))
    )
    (net (code "83") (name "Net-(U522-~{OUT4})") (class "Default")
      (node (ref "D522") (pin "1") (pinfunction "1_1") (pintype "passive"))
      (node (ref "U522") (pin "11") (pinfunction "~{OUT4}_11") (pintype "output"))
    )
    (net (code "84") (name "Net-(U522-~{OUT5})") (class "Default")
      (node (ref "D522") (pin "9") (pinfunction "9_9") (pintype "passive"))
      (node (ref "U522") (pin "12") (pinfunction "~{OUT5}_12") (pintype "output"))
    )
    (net (code "85") (name "Net-(U522-~{OUT6})") (class "Default")
      (node (ref "D522") (pin "10") (pinfunction "10_10") (pintype "passive"))
      (node (ref "U522") (pin "14") (pinfunction "~{OUT6}_14") (pintype "output"))
    )
    (net (code "86") (name "Net-(U522-~{OUT7})") (class "Default")
      (node (ref "D522") (pin "5") (pinfunction "5_5") (pintype "passive"))
      (node (ref "U522") (pin "15") (pinfunction "~{OUT7}_15") (pintype "output"))
    )
    (net (code "87") (name "Net-(U523-REXT)") (class "Default")
      (node (ref "R523") (pin "1") (pinfunction "1_1") (pintype "passive"))
      (node (ref "U523") (pin "1") (pinfunction "REXT_1") (pintype "input"))
    )
    (net (code "88") (name "Net-(U523-~{OUT0})") (class "Default")
      (node (ref "D523") (pin "7") (pinfunction "7_7") (pintype "passive"))
      (node (ref "U523") (pin "6") (pinfunction "~{OUT0}_6") (pintype "output"))
    )
    (net (code "89") (name "Net-(U523-~{OUT1})") (class "Default")
      (node (ref "D523") (pin "6") (pinfunction "6_6") (pintype "passive"))
      (node (ref "U523") (pin "7") (pinfunction "~{OUT1}_7") (pintype "output"))
    )
    (net (code "90") (name "Net-(U523-~{OUT2})") (class "Default")
      (node (ref "D523") (pin "4") (pinfunction "4_4") (pintype "passive"))
      (node (ref "U523") (pin "9") (pinfunction "~{OUT2}_9") (pintype "output"))
    )
    (net (code "91") (name "Net-(U523-~{OUT3})") (class "Default")
      (node (ref "D523") (pin "2") (pinfunction "2_2") (pintype "passive"))
      (node (ref "U523") (pin "10") (pinfunction "~{OUT3}_10") (pintype "output"))
    )
    (net (code "92") (name "Net-(U523-~{OUT4})") (class "Default")
      (node (ref "D523") (pin "1") (pinfunction "1_1") (pintype "passive"))
      (node (ref "U523") (pin "11") (pinfunction "~{OUT4}_11") (pintype "output"))
    )
    (net (code "93") (name "Net-(U523-~{OUT5})") (class "Default")
      (node (ref "D523") (pin "9") (pinfunction "9_9") (pintype "passive"))
      (node (ref "U523") (pin "12") (pinfunction "~{OUT5}_12") (pintype "output"))
    )
    (net (code "94") (name "Net-(U523-~{OUT6})") (class "Default")
      (node (ref "D523") (pin "10") (pinfunction "10_10") (pintype "passive"))
      (node (ref "U523") (pin "14") (pinfunction "~{OUT6}_14") (pintype "output"))
    )
    (net (code "95") (name "Net-(U523-~{OUT7})") (class "Default")
      (node (ref "D523") (pin "5") (pinfunction "5_5") (pintype "passive"))
      (node (ref "U523") (pin "15") (pinfunction "~{OUT7}_15") (pintype "output"))
    )
  )
)
